# devBoard.net
KiCad netlist of a schematic drawn in EAGLE
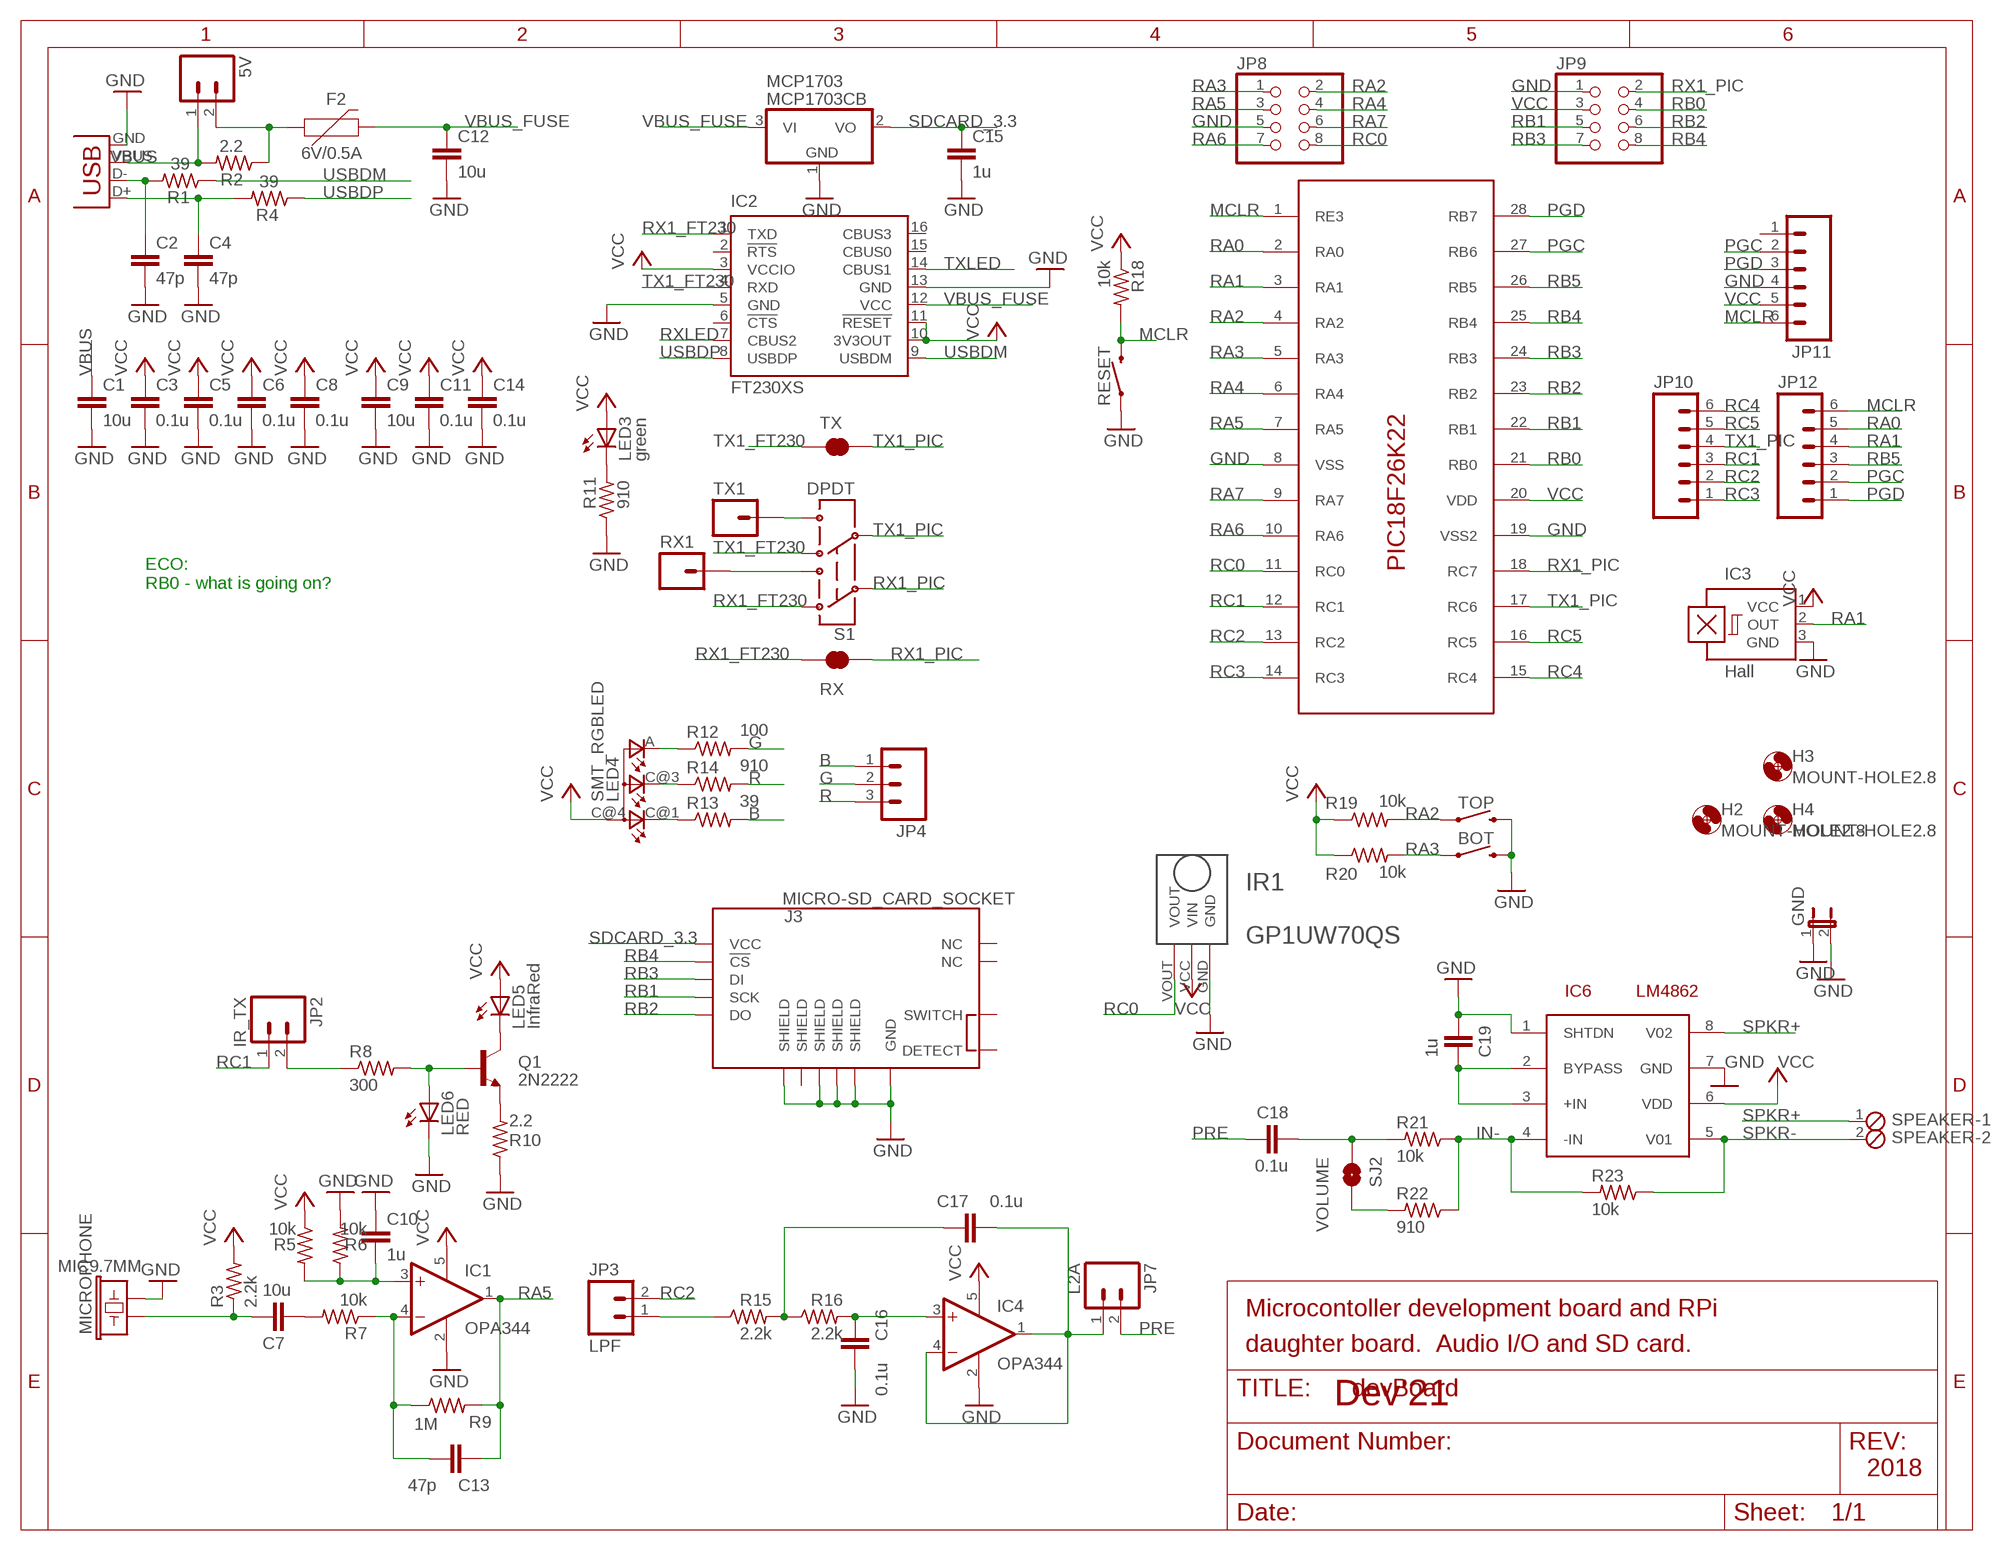
[diagram p0: schematic, sheet 1]

(export (version "E")
  (design (tool "Eeschema 10.0.6"))
  (components
    (comp (ref "5V")
      (value "M02LOCK")
      (footprint "eagle-import:1X02_LOCK")
      (libsource (lib "eagle-import") (part "M02LOCK"))
    )
    (comp (ref "BOT")
      (value "MOMENTARY-SWITCH-SPST-SMD-5.2MM")
      (footprint "eagle-import:TACTILE_SWITCH_SMD_5.2MM")
      (libsource (lib "eagle-import") (part "MOMENTARY-SWITCH-SPST-SMD-5.2MM"))
    )
    (comp (ref "C1")
      (value "10u")
      (footprint "eagle-import:C1206")
      (libsource (lib "eagle-import") (part "C-EUC1206"))
    )
    (comp (ref "C2")
      (value "47p")
      (footprint "eagle-import:C1206")
      (libsource (lib "eagle-import") (part "C-EUC1206"))
    )
    (comp (ref "C3")
      (value "0.1u")
      (footprint "eagle-import:C1206")
      (libsource (lib "eagle-import") (part "C-EUC1206"))
    )
    (comp (ref "C4")
      (value "47p")
      (footprint "eagle-import:C1206")
      (libsource (lib "eagle-import") (part "C-EUC1206"))
    )
    (comp (ref "C5")
      (value "0.1u")
      (footprint "eagle-import:C1206")
      (libsource (lib "eagle-import") (part "C-EUC1206"))
    )
    (comp (ref "C6")
      (value "0.1u")
      (footprint "eagle-import:C1206")
      (libsource (lib "eagle-import") (part "C-EUC1206"))
    )
    (comp (ref "C7")
      (value "10u")
      (footprint "eagle-import:C1206")
      (libsource (lib "eagle-import") (part "C-EUC1206"))
    )
    (comp (ref "C8")
      (value "0.1u")
      (footprint "eagle-import:C1206")
      (libsource (lib "eagle-import") (part "C-EUC1206"))
    )
    (comp (ref "C9")
      (value "10u")
      (footprint "eagle-import:C1206")
      (libsource (lib "eagle-import") (part "C-EUC1206"))
    )
    (comp (ref "C10")
      (value "1u")
      (footprint "eagle-import:C1206")
      (libsource (lib "eagle-import") (part "C-EUC1206"))
    )
    (comp (ref "C11")
      (value "0.1u")
      (footprint "eagle-import:C1206")
      (libsource (lib "eagle-import") (part "C-EUC1206"))
    )
    (comp (ref "C12")
      (value "10u")
      (footprint "eagle-import:C1206")
      (libsource (lib "eagle-import") (part "C-EUC1206"))
    )
    (comp (ref "C13")
      (value "47p")
      (footprint "eagle-import:C1206")
      (libsource (lib "eagle-import") (part "C-EUC1206"))
    )
    (comp (ref "C14")
      (value "0.1u")
      (footprint "eagle-import:C1206")
      (libsource (lib "eagle-import") (part "C-EUC1206"))
    )
    (comp (ref "C15")
      (value "1u")
      (footprint "eagle-import:C1206")
      (libsource (lib "eagle-import") (part "C-EUC1206"))
    )
    (comp (ref "C16")
      (value "0.1u")
      (footprint "eagle-import:C1206")
      (libsource (lib "eagle-import") (part "C-EUC1206"))
    )
    (comp (ref "C17")
      (value "0.1u")
      (footprint "eagle-import:C1206")
      (libsource (lib "eagle-import") (part "C-EUC1206"))
    )
    (comp (ref "C18")
      (value "0.1u")
      (footprint "eagle-import:C1206")
      (libsource (lib "eagle-import") (part "C-EUC1206"))
    )
    (comp (ref "C19")
      (value "1u")
      (footprint "eagle-import:C1206")
      (libsource (lib "eagle-import") (part "C-EUC1206"))
    )
    (comp (ref "F2")
      (value "6V/0.5A")
      (footprint "eagle-import:1206")
      (libsource (lib "eagle-import") (part "PPTC_6V500MA-2"))
    )
    (comp (ref "GND")
      (value "JP1E")
      (footprint "eagle-import:JP1")
      (libsource (lib "eagle-import") (part "JP1E"))
    )
    (comp (ref "H2")
      (value "MOUNT-HOLE2.8")
      (footprint "eagle-import:2,8")
      (libsource (lib "eagle-import") (part "MOUNT-HOLE2.8"))
    )
    (comp (ref "H3")
      (value "MOUNT-HOLE2.8")
      (footprint "eagle-import:2,8")
      (libsource (lib "eagle-import") (part "MOUNT-HOLE2.8"))
    )
    (comp (ref "H4")
      (value "MOUNT-HOLE2.8")
      (footprint "eagle-import:2,8")
      (libsource (lib "eagle-import") (part "MOUNT-HOLE2.8"))
    )
    (comp (ref "IC1")
      (value "OPA344")
      (footprint "eagle-import:SOT23-5")
      (libsource (lib "eagle-import") (part "OPA-SOT23344N"))
    )
    (comp (ref "IC2")
      (value "FT230XS")
      (footprint "eagle-import:SSOP16")
      (libsource (lib "eagle-import") (part "FT230XS"))
    )
    (comp (ref "IC3")
      (value "Hall")
      (footprint "eagle-import:SOT23-W")
      (libsource (lib "eagle-import") (part "A12?LH02"))
    )
    (comp (ref "IC4")
      (value "OPA344")
      (footprint "eagle-import:SOT23-5")
      (libsource (lib "eagle-import") (part "OPA-SOT23344N"))
    )
    (comp (ref "IC6")
      (value "LM4862")
      (footprint "eagle-import:SO08")
      (libsource (lib "eagle-import") (part "LM4862"))
    )
    (comp (ref "IR1")
      (value "GP1UW70QS")
      (footprint "eagle-import:GP1UW70QS")
      (libsource (lib "eagle-import") (part "GP1UW70QS"))
    )
    (comp (ref "J3")
      (value "MICRO-SD_CARD_SOCKET")
      (footprint "eagle-import:MICRO-SD-SOCKET")
      (libsource (lib "eagle-import") (part "MICRO-SD_CARD_SOCKET"))
    )
    (comp (ref "JP2")
      (value "IR_TX")
      (footprint "eagle-import:1X02_LOCK")
      (libsource (lib "eagle-import") (part "M02LOCK"))
    )
    (comp (ref "JP3")
      (value "LPF")
      (footprint "eagle-import:1X02_LOCK")
      (libsource (lib "eagle-import") (part "M02LOCK"))
    )
    (comp (ref "JP4")
      (value "M03LOCK")
      (footprint "eagle-import:1X03_LOCK")
      (libsource (lib "eagle-import") (part "M03LOCK"))
    )
    (comp (ref "JP7")
      (value "L2A")
      (footprint "eagle-import:1X02_LOCK")
      (libsource (lib "eagle-import") (part "M02LOCK"))
    )
    (comp (ref "JP8")
      (value "PINHD-2X4")
      (footprint "eagle-import:2X04")
      (libsource (lib "eagle-import") (part "PINHD-2X4"))
    )
    (comp (ref "JP9")
      (value "PINHD-2X4")
      (footprint "eagle-import:2X04")
      (libsource (lib "eagle-import") (part "PINHD-2X4"))
    )
    (comp (ref "JP10")
      (value "M06LOCK")
      (footprint "eagle-import:1X06_LOCK")
      (libsource (lib "eagle-import") (part "M06LOCK"))
    )
    (comp (ref "JP11")
      (value "M06LOCK")
      (footprint "eagle-import:1X06_LOCK")
      (libsource (lib "eagle-import") (part "M06LOCK"))
    )
    (comp (ref "JP12")
      (value "M06LOCK")
      (footprint "eagle-import:1X06_LOCK")
      (libsource (lib "eagle-import") (part "M06LOCK"))
    )
    (comp (ref "LED3")
      (value "green")
      (footprint "eagle-import:LED-1206")
      (libsource (lib "eagle-import") (part "LED1206"))
    )
    (comp (ref "LED4")
      (value "SMT_RGBLED")
      (footprint "eagle-import:P-LCC-4")
      (libsource (lib "eagle-import") (part "SMT_RGBLED"))
    )
    (comp (ref "LED5")
      (value "InfraRed")
      (footprint "eagle-import:LED-1206")
      (libsource (lib "eagle-import") (part "LED1206"))
    )
    (comp (ref "LED6")
      (value "RED")
      (footprint "eagle-import:LED-1206")
      (libsource (lib "eagle-import") (part "LED1206"))
    )
    (comp (ref "MCP1703")
      (value "MCP1703CB")
      (footprint "eagle-import:SOT23")
      (libsource (lib "eagle-import") (part "MCP1703CB"))
    )
    (comp (ref "MICROPHONE")
      (value "MIC9.7MM")
      (footprint "eagle-import:MIC-9.7MM")
      (libsource (lib "eagle-import") (part "MIC9.7MM"))
    )
    (comp (ref "PIC18F26K22")
      (value "PIC18F26J2228SSOP")
      (footprint "eagle-import:SSOP28DB")
      (libsource (lib "eagle-import") (part "PIC18F26J2228SSOP"))
    )
    (comp (ref "Q1")
      (value "2N2222")
      (footprint "eagle-import:SOT23-3")
      (libsource (lib "eagle-import") (part "TRANSISTOR_NPNSOT23-3"))
    )
    (comp (ref "R1")
      (value "39")
      (footprint "eagle-import:R1206")
      (libsource (lib "eagle-import") (part "R-US_R1206"))
    )
    (comp (ref "R2")
      (value "2.2")
      (footprint "eagle-import:R1206")
      (libsource (lib "eagle-import") (part "R-US_R1206"))
    )
    (comp (ref "R3")
      (value "2.2k")
      (footprint "eagle-import:R1206")
      (libsource (lib "eagle-import") (part "R-US_R1206"))
    )
    (comp (ref "R4")
      (value "39")
      (footprint "eagle-import:R1206")
      (libsource (lib "eagle-import") (part "R-US_R1206"))
    )
    (comp (ref "R5")
      (value "10k")
      (footprint "eagle-import:R1206")
      (libsource (lib "eagle-import") (part "R-US_R1206"))
    )
    (comp (ref "R6")
      (value "10k")
      (footprint "eagle-import:R1206")
      (libsource (lib "eagle-import") (part "R-US_R1206"))
    )
    (comp (ref "R7")
      (value "10k")
      (footprint "eagle-import:R1206")
      (libsource (lib "eagle-import") (part "R-US_R1206"))
    )
    (comp (ref "R8")
      (value "300")
      (footprint "eagle-import:R1206")
      (libsource (lib "eagle-import") (part "R-US_R1206"))
    )
    (comp (ref "R9")
      (value "1M")
      (footprint "eagle-import:R1206")
      (libsource (lib "eagle-import") (part "R-US_R1206"))
    )
    (comp (ref "R10")
      (value "2.2")
      (footprint "eagle-import:R1206")
      (libsource (lib "eagle-import") (part "R-US_R1206"))
    )
    (comp (ref "R11")
      (value "910")
      (footprint "eagle-import:R1206")
      (libsource (lib "eagle-import") (part "R-US_R1206"))
    )
    (comp (ref "R12")
      (value "100")
      (footprint "eagle-import:R1206")
      (libsource (lib "eagle-import") (part "R-US_R1206"))
    )
    (comp (ref "R13")
      (value "39")
      (footprint "eagle-import:R1206")
      (libsource (lib "eagle-import") (part "R-US_R1206"))
    )
    (comp (ref "R14")
      (value "910")
      (footprint "eagle-import:R1206")
      (libsource (lib "eagle-import") (part "R-US_R1206"))
    )
    (comp (ref "R15")
      (value "2.2k")
      (footprint "eagle-import:R1206")
      (libsource (lib "eagle-import") (part "R-US_R1206"))
    )
    (comp (ref "R16")
      (value "2.2k")
      (footprint "eagle-import:R1206")
      (libsource (lib "eagle-import") (part "R-US_R1206"))
    )
    (comp (ref "R18")
      (value "10k")
      (footprint "eagle-import:R1206")
      (libsource (lib "eagle-import") (part "R-US_R1206"))
    )
    (comp (ref "R19")
      (value "10k")
      (footprint "eagle-import:R1206")
      (libsource (lib "eagle-import") (part "R-US_R1206"))
    )
    (comp (ref "R20")
      (value "10k")
      (footprint "eagle-import:R1206")
      (libsource (lib "eagle-import") (part "R-US_R1206"))
    )
    (comp (ref "R21")
      (value "10k")
      (footprint "eagle-import:R1206")
      (libsource (lib "eagle-import") (part "R-US_R1206"))
    )
    (comp (ref "R22")
      (value "910")
      (footprint "eagle-import:R1206")
      (libsource (lib "eagle-import") (part "R-US_R1206"))
    )
    (comp (ref "R23")
      (value "10k")
      (footprint "eagle-import:R1206")
      (libsource (lib "eagle-import") (part "R-US_R1206"))
    )
    (comp (ref "RESET")
      (value "MOMENTARY-SWITCH-SPST-SMD-5.2MM")
      (footprint "eagle-import:TACTILE_SWITCH_SMD_5.2MM")
      (libsource (lib "eagle-import") (part "MOMENTARY-SWITCH-SPST-SMD-5.2MM"))
    )
    (comp (ref "RX")
      (value "SJ_NC")
      (footprint "eagle-import:SMT-JUMPER_2_NC_TRACE_NO-SILK")
      (libsource (lib "eagle-import") (part "JUMPER-SMT_2_NC_TRACE_NO-SILK"))
    )
    (comp (ref "RX1")
      (value "M01PTH")
      (footprint "eagle-import:1X01")
      (libsource (lib "eagle-import") (part "M01PTH"))
    )
    (comp (ref "S1")
      (value "DPDT")
      (footprint "eagle-import:AYZ0202")
      (libsource (lib "eagle-import") (part "SWITCH-DPDTAYZ0202"))
    )
    (comp (ref "SJ2")
      (value "VOLUME")
      (footprint "eagle-import:SJ_2S-NOTRACE")
      (libsource (lib "eagle-import") (part "SOLDERJUMPERNC2"))
    )
    (comp (ref "SPEAKER")
      (value "MPT2")
      (footprint "eagle-import:2POL254")
      (libsource (lib "eagle-import") (part "MPT2"))
    )
    (comp (ref "TOP")
      (value "MOMENTARY-SWITCH-SPST-SMD-5.2MM")
      (footprint "eagle-import:TACTILE_SWITCH_SMD_5.2MM")
      (libsource (lib "eagle-import") (part "MOMENTARY-SWITCH-SPST-SMD-5.2MM"))
    )
    (comp (ref "TX")
      (value "SJ_NC")
      (footprint "eagle-import:SMT-JUMPER_2_NC_TRACE_NO-SILK")
      (libsource (lib "eagle-import") (part "JUMPER-SMT_2_NC_TRACE_NO-SILK"))
    )
    (comp (ref "TX1")
      (value "M01PTH")
      (footprint "eagle-import:1X01")
      (libsource (lib "eagle-import") (part "M01PTH"))
    )
    (comp (ref "X1")
      (value "USBSMD")
      (footprint "eagle-import:USB-MINIB")
      (libsource (lib "eagle-import") (part "USBSMD"))
    )
  )
  (nets
    (net (code "1") (name "/B") (class "Default")
      (node (ref "JP4") (pin "1") (pinfunction "1_1") (pintype "passive"))
      (node (ref "R13") (pin "2") (pinfunction "2_2") (pintype "passive"))
    )
    (net (code "2") (name "/G") (class "Default")
      (node (ref "JP4") (pin "2") (pinfunction "2_2") (pintype "passive"))
      (node (ref "R12") (pin "2") (pinfunction "2_2") (pintype "passive"))
    )
    (net (code "3") (name "/IN-") (class "Default")
      (node (ref "IC6") (pin "4") (pinfunction "-IN_4") (pintype "bidirectional"))
      (node (ref "R21") (pin "1") (pinfunction "1_1") (pintype "passive"))
      (node (ref "R22") (pin "1") (pinfunction "1_1") (pintype "passive"))
      (node (ref "R23") (pin "2") (pinfunction "2_2") (pintype "passive"))
    )
    (net (code "4") (name "/MCLR") (class "Default")
      (node (ref "JP11") (pin "6") (pinfunction "6_6") (pintype "passive"))
      (node (ref "JP12") (pin "6") (pinfunction "6_6") (pintype "passive"))
      (node (ref "PIC18F26K22") (pin "1") (pinfunction "RE3_1") (pintype "bidirectional"))
      (node (ref "R18") (pin "2") (pinfunction "2_2") (pintype "passive"))
      (node (ref "RESET") (pin "3") (pinfunction "2_3") (pintype "passive"))
    )
    (net (code "5") (name "/PGC") (class "Default")
      (node (ref "JP11") (pin "2") (pinfunction "2_2") (pintype "passive"))
      (node (ref "JP12") (pin "2") (pinfunction "2_2") (pintype "passive"))
      (node (ref "PIC18F26K22") (pin "27") (pinfunction "RB6_27") (pintype "bidirectional"))
    )
    (net (code "6") (name "/PGD") (class "Default")
      (node (ref "JP11") (pin "3") (pinfunction "3_3") (pintype "passive"))
      (node (ref "JP12") (pin "1") (pinfunction "1_1") (pintype "passive"))
      (node (ref "PIC18F26K22") (pin "28") (pinfunction "RB7_28") (pintype "bidirectional"))
    )
    (net (code "7") (name "/PRE") (class "Default")
      (node (ref "C18") (pin "2") (pinfunction "2_2") (pintype "passive"))
      (node (ref "JP7") (pin "2") (pinfunction "2_2") (pintype "passive"))
    )
    (net (code "8") (name "/R") (class "Default")
      (node (ref "JP4") (pin "3") (pinfunction "3_3") (pintype "passive"))
      (node (ref "R14") (pin "2") (pinfunction "2_2") (pintype "passive"))
    )
    (net (code "9") (name "/RA0") (class "Default")
      (node (ref "JP12") (pin "5") (pinfunction "5_5") (pintype "passive"))
      (node (ref "PIC18F26K22") (pin "2") (pinfunction "RA0_2") (pintype "bidirectional"))
    )
    (net (code "10") (name "/RA1") (class "Default")
      (node (ref "IC3") (pin "2") (pinfunction "OUT_2") (pintype "output"))
      (node (ref "JP12") (pin "4") (pinfunction "4_4") (pintype "passive"))
      (node (ref "PIC18F26K22") (pin "3") (pinfunction "RA1_3") (pintype "bidirectional"))
    )
    (net (code "11") (name "/RA2") (class "Default")
      (node (ref "JP8") (pin "2") (pinfunction "2_2") (pintype "passive"))
      (node (ref "PIC18F26K22") (pin "4") (pinfunction "RA2_4") (pintype "bidirectional"))
      (node (ref "R19") (pin "2") (pinfunction "2_2") (pintype "passive"))
      (node (ref "TOP") (pin "1") (pinfunction "1_1") (pintype "passive"))
    )
    (net (code "12") (name "/RA3") (class "Default")
      (node (ref "BOT") (pin "1") (pinfunction "1_1") (pintype "passive"))
      (node (ref "JP8") (pin "1") (pinfunction "1_1") (pintype "passive"))
      (node (ref "PIC18F26K22") (pin "5") (pinfunction "RA3_5") (pintype "bidirectional"))
      (node (ref "R20") (pin "2") (pinfunction "2_2") (pintype "passive"))
    )
    (net (code "13") (name "/RA4") (class "Default")
      (node (ref "JP8") (pin "4") (pinfunction "4_4") (pintype "passive"))
      (node (ref "PIC18F26K22") (pin "6") (pinfunction "RA4_6") (pintype "bidirectional"))
    )
    (net (code "14") (name "/RA5") (class "Default")
      (node (ref "C13") (pin "2") (pinfunction "2_2") (pintype "passive"))
      (node (ref "IC1") (pin "1") (pinfunction "OUT_1") (pintype "output"))
      (node (ref "JP8") (pin "3") (pinfunction "3_3") (pintype "passive"))
      (node (ref "PIC18F26K22") (pin "7") (pinfunction "RA5_7") (pintype "bidirectional"))
      (node (ref "R9") (pin "2") (pinfunction "2_2") (pintype "passive"))
    )
    (net (code "15") (name "/RA6") (class "Default")
      (node (ref "JP8") (pin "7") (pinfunction "7_7") (pintype "passive"))
      (node (ref "PIC18F26K22") (pin "10") (pinfunction "RA6_10") (pintype "bidirectional"))
    )
    (net (code "16") (name "/RA7") (class "Default")
      (node (ref "JP8") (pin "6") (pinfunction "6_6") (pintype "passive"))
      (node (ref "PIC18F26K22") (pin "9") (pinfunction "RA7_9") (pintype "bidirectional"))
    )
    (net (code "17") (name "/RB0") (class "Default")
      (node (ref "JP9") (pin "4") (pinfunction "4_4") (pintype "passive"))
      (node (ref "PIC18F26K22") (pin "21") (pinfunction "RB0_21") (pintype "bidirectional"))
    )
    (net (code "18") (name "/RB1") (class "Default")
      (node (ref "J3") (pin "SCLK") (pinfunction "SCK_SCLK") (pintype "bidirectional"))
      (node (ref "JP9") (pin "5") (pinfunction "5_5") (pintype "passive"))
      (node (ref "PIC18F26K22") (pin "22") (pinfunction "RB1_22") (pintype "bidirectional"))
    )
    (net (code "19") (name "/RB2") (class "Default")
      (node (ref "J3") (pin "DO") (pinfunction "DO_DO") (pintype "bidirectional"))
      (node (ref "JP9") (pin "6") (pinfunction "6_6") (pintype "passive"))
      (node (ref "PIC18F26K22") (pin "23") (pinfunction "RB2_23") (pintype "bidirectional"))
    )
    (net (code "20") (name "/RB3") (class "Default")
      (node (ref "J3") (pin "DI") (pinfunction "DI_DI") (pintype "bidirectional"))
      (node (ref "JP9") (pin "7") (pinfunction "7_7") (pintype "passive"))
      (node (ref "PIC18F26K22") (pin "24") (pinfunction "RB3_24") (pintype "bidirectional"))
    )
    (net (code "21") (name "/RB4") (class "Default")
      (node (ref "J3") (pin "CS") (pinfunction "~{CS}_CS") (pintype "bidirectional"))
      (node (ref "JP9") (pin "8") (pinfunction "8_8") (pintype "passive"))
      (node (ref "PIC18F26K22") (pin "25") (pinfunction "RB4_25") (pintype "bidirectional"))
    )
    (net (code "22") (name "/RB5") (class "Default")
      (node (ref "JP12") (pin "3") (pinfunction "3_3") (pintype "passive"))
      (node (ref "PIC18F26K22") (pin "26") (pinfunction "RB5_26") (pintype "bidirectional"))
    )
    (net (code "23") (name "/RC0") (class "Default")
      (node (ref "IR1") (pin "VOUT") (pinfunction "VOUT_VOUT") (pintype "bidirectional"))
      (node (ref "JP8") (pin "8") (pinfunction "8_8") (pintype "passive"))
      (node (ref "PIC18F26K22") (pin "11") (pinfunction "RC0_11") (pintype "bidirectional"))
    )
    (net (code "24") (name "/RC1") (class "Default")
      (node (ref "JP10") (pin "3") (pinfunction "3_3") (pintype "passive"))
      (node (ref "JP2") (pin "1") (pinfunction "1_1") (pintype "passive"))
      (node (ref "PIC18F26K22") (pin "12") (pinfunction "RC1_12") (pintype "bidirectional"))
    )
    (net (code "25") (name "/RC2") (class "Default")
      (node (ref "JP10") (pin "2") (pinfunction "2_2") (pintype "passive"))
      (node (ref "JP3") (pin "2") (pinfunction "2_2") (pintype "passive"))
      (node (ref "PIC18F26K22") (pin "13") (pinfunction "RC2_13") (pintype "bidirectional"))
    )
    (net (code "26") (name "/RC3") (class "Default")
      (node (ref "JP10") (pin "1") (pinfunction "1_1") (pintype "passive"))
      (node (ref "PIC18F26K22") (pin "14") (pinfunction "RC3_14") (pintype "bidirectional"))
    )
    (net (code "27") (name "/RC4") (class "Default")
      (node (ref "JP10") (pin "6") (pinfunction "6_6") (pintype "passive"))
      (node (ref "PIC18F26K22") (pin "15") (pinfunction "RC4_15") (pintype "bidirectional"))
    )
    (net (code "28") (name "/RC5") (class "Default")
      (node (ref "JP10") (pin "5") (pinfunction "5_5") (pintype "passive"))
      (node (ref "PIC18F26K22") (pin "16") (pinfunction "RC5_16") (pintype "bidirectional"))
    )
    (net (code "29") (name "/RX1_FT230") (class "Default")
      (node (ref "IC2") (pin "1") (pinfunction "TXD_1") (pintype "output"))
      (node (ref "RX") (pin "1") (pinfunction "1_1") (pintype "passive"))
      (node (ref "S1") (pin "1") (pinfunction "1_1") (pintype "bidirectional"))
    )
    (net (code "30") (name "/RX1_PIC") (class "Default")
      (node (ref "JP9") (pin "2") (pinfunction "2_2") (pintype "passive"))
      (node (ref "PIC18F26K22") (pin "18") (pinfunction "RC7_18") (pintype "bidirectional"))
      (node (ref "RX") (pin "2") (pinfunction "2_2") (pintype "passive"))
      (node (ref "S1") (pin "2") (pinfunction "2_2") (pintype "bidirectional"))
    )
    (net (code "31") (name "/RXLED") (class "Default")
      (node (ref "IC2") (pin "7") (pinfunction "CBUS2_7") (pintype "bidirectional"))
    )
    (net (code "32") (name "/SDCARD_3.3") (class "Default")
      (node (ref "C15") (pin "1") (pinfunction "1_1") (pintype "passive"))
      (node (ref "J3") (pin "VCC") (pinfunction "VCC_VCC") (pintype "bidirectional"))
      (node (ref "MCP1703") (pin "2") (pinfunction "VO_2") (pintype "passive"))
    )
    (net (code "33") (name "/SPKR+") (class "Default")
      (node (ref "IC6") (pin "8") (pinfunction "V02_8") (pintype "bidirectional"))
      (node (ref "SPEAKER") (pin "1") (pinfunction "1_1") (pintype "passive"))
    )
    (net (code "34") (name "/SPKR-") (class "Default")
      (node (ref "IC6") (pin "5") (pinfunction "V01_5") (pintype "bidirectional"))
      (node (ref "R23") (pin "1") (pinfunction "1_1") (pintype "passive"))
      (node (ref "SPEAKER") (pin "2") (pinfunction "1_2") (pintype "passive"))
    )
    (net (code "35") (name "/TX1_FT230") (class "Default")
      (node (ref "IC2") (pin "4") (pinfunction "RXD_4") (pintype "input"))
      (node (ref "S1") (pin "4") (pinfunction "4_4") (pintype "bidirectional"))
      (node (ref "TX") (pin "1") (pinfunction "1_1") (pintype "passive"))
    )
    (net (code "36") (name "/TX1_PIC") (class "Default")
      (node (ref "JP10") (pin "4") (pinfunction "4_4") (pintype "passive"))
      (node (ref "PIC18F26K22") (pin "17") (pinfunction "RC6_17") (pintype "bidirectional"))
      (node (ref "S1") (pin "5") (pinfunction "5_5") (pintype "bidirectional"))
      (node (ref "TX") (pin "2") (pinfunction "2_2") (pintype "passive"))
    )
    (net (code "37") (name "/TXLED") (class "Default")
      (node (ref "IC2") (pin "14") (pinfunction "CBUS1_14") (pintype "bidirectional"))
    )
    (net (code "38") (name "/USBDM") (class "Default")
      (node (ref "IC2") (pin "9") (pinfunction "USBDM_9") (pintype "input"))
      (node (ref "R1") (pin "1") (pinfunction "1_1") (pintype "passive"))
    )
    (net (code "39") (name "/USBDP") (class "Default")
      (node (ref "IC2") (pin "8") (pinfunction "USBDP_8") (pintype "input"))
      (node (ref "R4") (pin "1") (pinfunction "1_1") (pintype "passive"))
    )
    (net (code "40") (name "/VBUS") (class "Default")
      (node (ref "5V") (pin "1") (pinfunction "1_1") (pintype "passive"))
      (node (ref "C1") (pin "1") (pinfunction "1_1") (pintype "passive"))
      (node (ref "R2") (pin "2") (pinfunction "2_2") (pintype "passive"))
      (node (ref "X1") (pin "VBUS") (pinfunction "VBUS_VBUS") (pintype "bidirectional"))
    )
    (net (code "41") (name "/VBUS_FUSE") (class "Default")
      (node (ref "C12") (pin "1") (pinfunction "1_1") (pintype "passive"))
      (node (ref "F2") (pin "2") (pinfunction "2_2") (pintype "bidirectional"))
      (node (ref "IC2") (pin "12") (pinfunction "VCC_12") (pintype "power_in"))
      (node (ref "MCP1703") (pin "3") (pinfunction "VI_3") (pintype "input"))
    )
    (net (code "42") (name "GND") (class "Default")
      (node (ref "BOT") (pin "3") (pinfunction "2_3") (pintype "passive"))
      (node (ref "C1") (pin "2") (pinfunction "2_2") (pintype "passive"))
      (node (ref "C10") (pin "1") (pinfunction "1_1") (pintype "passive"))
      (node (ref "C11") (pin "2") (pinfunction "2_2") (pintype "passive"))
      (node (ref "C12") (pin "2") (pinfunction "2_2") (pintype "passive"))
      (node (ref "C14") (pin "2") (pinfunction "2_2") (pintype "passive"))
      (node (ref "C15") (pin "2") (pinfunction "2_2") (pintype "passive"))
      (node (ref "C16") (pin "1") (pinfunction "1_1") (pintype "passive"))
      (node (ref "C19") (pin "2") (pinfunction "2_2") (pintype "passive"))
      (node (ref "C2") (pin "2") (pinfunction "2_2") (pintype "passive"))
      (node (ref "C3") (pin "2") (pinfunction "2_2") (pintype "passive"))
      (node (ref "C4") (pin "2") (pinfunction "2_2") (pintype "passive"))
      (node (ref "C5") (pin "2") (pinfunction "2_2") (pintype "passive"))
      (node (ref "C6") (pin "2") (pinfunction "2_2") (pintype "passive"))
      (node (ref "C8") (pin "2") (pinfunction "2_2") (pintype "passive"))
      (node (ref "C9") (pin "2") (pinfunction "2_2") (pintype "passive"))
      (node (ref "GND") (pin "1") (pinfunction "1_1") (pintype "passive"))
      (node (ref "GND") (pin "2") (pinfunction "2_2") (pintype "passive"))
      (node (ref "IC1") (pin "2") (pinfunction "V-_2") (pintype "power_in"))
      (node (ref "IC2") (pin "13") (pinfunction "GND_13") (pintype "power_in"))
      (node (ref "IC2") (pin "5") (pinfunction "GND_5") (pintype "power_in"))
      (node (ref "IC3") (pin "3") (pinfunction "GND_3") (pintype "power_in"))
      (node (ref "IC4") (pin "2") (pinfunction "V-_2") (pintype "power_in"))
      (node (ref "IC6") (pin "1") (pinfunction "SHTDN_1") (pintype "bidirectional"))
      (node (ref "IC6") (pin "7") (pinfunction "GND_7") (pintype "power_in"))
      (node (ref "IR1") (pin "GND") (pinfunction "GND_GND") (pintype "bidirectional"))
      (node (ref "J3") (pin "GND") (pinfunction "GND_GND") (pintype "bidirectional"))
      (node (ref "J3") (pin "SHIELD1") (pinfunction "SHIELD_SHIELD1") (pintype "bidirectional"))
      (node (ref "J3") (pin "SHIELD3") (pinfunction "SHIELD_SHIELD3") (pintype "bidirectional"))
      (node (ref "J3") (pin "SHIELD4") (pinfunction "SHIELD_SHIELD4") (pintype "bidirectional"))
      (node (ref "J3") (pin "SHIELD5") (pinfunction "SHIELD_SHIELD5") (pintype "bidirectional"))
      (node (ref "JP11") (pin "4") (pinfunction "4_4") (pintype "passive"))
      (node (ref "JP8") (pin "5") (pinfunction "5_5") (pintype "passive"))
      (node (ref "JP9") (pin "1") (pinfunction "1_1") (pintype "passive"))
      (node (ref "LED6") (pin "C") (pinfunction "C_C") (pintype "passive"))
      (node (ref "MCP1703") (pin "1") (pinfunction "GND_1") (pintype "passive"))
      (node (ref "MICROPHONE") (pin "2") (pinfunction "2_2") (pintype "passive"))
      (node (ref "PIC18F26K22") (pin "19") (pinfunction "VSS2_19") (pintype "bidirectional"))
      (node (ref "PIC18F26K22") (pin "8") (pinfunction "VSS_8") (pintype "bidirectional"))
      (node (ref "R10") (pin "1") (pinfunction "1_1") (pintype "passive"))
      (node (ref "R11") (pin "1") (pinfunction "1_1") (pintype "passive"))
      (node (ref "R6") (pin "2") (pinfunction "2_2") (pintype "passive"))
      (node (ref "RESET") (pin "1") (pinfunction "1_1") (pintype "passive"))
      (node (ref "TOP") (pin "3") (pinfunction "2_3") (pintype "passive"))
      (node (ref "X1") (pin "GND") (pinfunction "GND_GND") (pintype "bidirectional"))
    )
    (net (code "43") (name "Net-(5V-Pad2)") (class "Default")
      (node (ref "5V") (pin "2") (pinfunction "2_2") (pintype "passive"))
      (node (ref "F2") (pin "1") (pinfunction "1_1") (pintype "bidirectional"))
      (node (ref "R2") (pin "1") (pinfunction "1_1") (pintype "passive"))
    )
    (net (code "44") (name "Net-(C2-Pad1)") (class "Default")
      (node (ref "C2") (pin "1") (pinfunction "1_1") (pintype "passive"))
      (node (ref "R1") (pin "2") (pinfunction "2_2") (pintype "passive"))
      (node (ref "X1") (pin "D-") (pinfunction "D-_D-") (pintype "bidirectional"))
    )
    (net (code "45") (name "Net-(C4-Pad1)") (class "Default")
      (node (ref "C4") (pin "1") (pinfunction "1_1") (pintype "passive"))
      (node (ref "R4") (pin "2") (pinfunction "2_2") (pintype "passive"))
      (node (ref "X1") (pin "D+") (pinfunction "D+_D+") (pintype "bidirectional"))
    )
    (net (code "46") (name "Net-(C7-Pad1)") (class "Default")
      (node (ref "C7") (pin "1") (pinfunction "1_1") (pintype "passive"))
      (node (ref "MICROPHONE") (pin "1") (pinfunction "1_1") (pintype "passive"))
      (node (ref "R3") (pin "1") (pinfunction "1_1") (pintype "passive"))
    )
    (net (code "47") (name "Net-(C7-Pad2)") (class "Default")
      (node (ref "C7") (pin "2") (pinfunction "2_2") (pintype "passive"))
      (node (ref "R7") (pin "2") (pinfunction "2_2") (pintype "passive"))
    )
    (net (code "48") (name "Net-(C17-Pad2)") (class "Default")
      (node (ref "C17") (pin "2") (pinfunction "2_2") (pintype "passive"))
      (node (ref "R15") (pin "2") (pinfunction "2_2") (pintype "passive"))
      (node (ref "R16") (pin "1") (pinfunction "1_1") (pintype "passive"))
    )
    (net (code "49") (name "Net-(C18-Pad1)") (class "Default")
      (node (ref "C18") (pin "1") (pinfunction "1_1") (pintype "passive"))
      (node (ref "R21") (pin "2") (pinfunction "2_2") (pintype "passive"))
      (node (ref "SJ2") (pin "1") (pinfunction "1_1") (pintype "passive"))
    )
    (net (code "50") (name "Net-(IC1-+IN)") (class "Default")
      (node (ref "C10") (pin "2") (pinfunction "2_2") (pintype "passive"))
      (node (ref "IC1") (pin "3") (pinfunction "+IN_3") (pintype "input"))
      (node (ref "R5") (pin "2") (pinfunction "2_2") (pintype "passive"))
      (node (ref "R6") (pin "1") (pinfunction "1_1") (pintype "passive"))
    )
    (net (code "51") (name "Net-(IC1--IN)") (class "Default")
      (node (ref "C13") (pin "1") (pinfunction "1_1") (pintype "passive"))
      (node (ref "IC1") (pin "4") (pinfunction "-IN_4") (pintype "input"))
      (node (ref "R7") (pin "1") (pinfunction "1_1") (pintype "passive"))
      (node (ref "R9") (pin "1") (pinfunction "1_1") (pintype "passive"))
    )
    (net (code "52") (name "Net-(IC4-+IN)") (class "Default")
      (node (ref "C16") (pin "2") (pinfunction "2_2") (pintype "passive"))
      (node (ref "IC4") (pin "3") (pinfunction "+IN_3") (pintype "input"))
      (node (ref "R16") (pin "2") (pinfunction "2_2") (pintype "passive"))
    )
    (net (code "53") (name "Net-(IC4--IN)") (class "Default")
      (node (ref "C17") (pin "1") (pinfunction "1_1") (pintype "passive"))
      (node (ref "IC4") (pin "1") (pinfunction "OUT_1") (pintype "output"))
      (node (ref "IC4") (pin "4") (pinfunction "-IN_4") (pintype "input"))
      (node (ref "JP7") (pin "1") (pinfunction "1_1") (pintype "passive"))
    )
    (net (code "54") (name "Net-(IC6-+IN)") (class "Default")
      (node (ref "C19") (pin "1") (pinfunction "1_1") (pintype "passive"))
      (node (ref "IC6") (pin "2") (pinfunction "BYPASS_2") (pintype "bidirectional"))
      (node (ref "IC6") (pin "3") (pinfunction "+IN_3") (pintype "bidirectional"))
    )
    (net (code "55") (name "Net-(JP2-Pad2)") (class "Default")
      (node (ref "JP2") (pin "2") (pinfunction "2_2") (pintype "passive"))
      (node (ref "R8") (pin "1") (pinfunction "1_1") (pintype "passive"))
    )
    (net (code "56") (name "Net-(JP3-Pad1)") (class "Default")
      (node (ref "JP3") (pin "1") (pinfunction "1_1") (pintype "passive"))
      (node (ref "R15") (pin "1") (pinfunction "1_1") (pintype "passive"))
    )
    (net (code "57") (name "Net-(LED3-PadC)") (class "Default")
      (node (ref "LED3") (pin "C") (pinfunction "C_C") (pintype "passive"))
      (node (ref "R11") (pin "2") (pinfunction "2_2") (pintype "passive"))
    )
    (net (code "58") (name "Net-(LED4-CBLUE)") (class "Default")
      (node (ref "LED4") (pin "C@3") (pinfunction "CBLUE_C@3") (pintype "passive"))
      (node (ref "R14") (pin "1") (pinfunction "1_1") (pintype "passive"))
    )
    (net (code "59") (name "Net-(LED4-CGREEN)") (class "Default")
      (node (ref "LED4") (pin "A") (pinfunction "CGREEN_A") (pintype "passive"))
      (node (ref "R12") (pin "1") (pinfunction "1_1") (pintype "passive"))
    )
    (net (code "60") (name "Net-(LED4-CRED)") (class "Default")
      (node (ref "LED4") (pin "C@1") (pinfunction "CRED_C@1") (pintype "passive"))
      (node (ref "R13") (pin "1") (pinfunction "1_1") (pintype "passive"))
    )
    (net (code "61") (name "Net-(Q1-B)") (class "Default")
      (node (ref "LED6") (pin "A") (pinfunction "A_A") (pintype "passive"))
      (node (ref "Q1") (pin "1") (pinfunction "B_1") (pintype "passive"))
      (node (ref "R8") (pin "2") (pinfunction "2_2") (pintype "passive"))
    )
    (net (code "62") (name "Net-(Q1-C)") (class "Default")
      (node (ref "LED5") (pin "C") (pinfunction "C_C") (pintype "passive"))
      (node (ref "Q1") (pin "3") (pinfunction "C_3") (pintype "passive"))
    )
    (net (code "63") (name "Net-(Q1-E)") (class "Default")
      (node (ref "Q1") (pin "2") (pinfunction "E_2") (pintype "passive"))
      (node (ref "R10") (pin "2") (pinfunction "2_2") (pintype "passive"))
    )
    (net (code "64") (name "Net-(R22-Pad2)") (class "Default")
      (node (ref "R22") (pin "2") (pinfunction "2_2") (pintype "passive"))
      (node (ref "SJ2") (pin "2") (pinfunction "2_2") (pintype "passive"))
    )
    (net (code "65") (name "Net-(RX1-Pad1)") (class "Default")
      (node (ref "RX1") (pin "1") (pinfunction "1_1") (pintype "passive"))
      (node (ref "S1") (pin "3") (pinfunction "3_3") (pintype "bidirectional"))
    )
    (net (code "66") (name "Net-(S1-Pad6)") (class "Default")
      (node (ref "S1") (pin "6") (pinfunction "6_6") (pintype "bidirectional"))
      (node (ref "TX1") (pin "1") (pinfunction "1_1") (pintype "passive"))
    )
    (net (code "67") (name "VCC") (class "Default")
      (node (ref "C11") (pin "1") (pinfunction "1_1") (pintype "passive"))
      (node (ref "C14") (pin "1") (pinfunction "1_1") (pintype "passive"))
      (node (ref "C3") (pin "1") (pinfunction "1_1") (pintype "passive"))
      (node (ref "C5") (pin "1") (pinfunction "1_1") (pintype "passive"))
      (node (ref "C6") (pin "1") (pinfunction "1_1") (pintype "passive"))
      (node (ref "C8") (pin "1") (pinfunction "1_1") (pintype "passive"))
      (node (ref "C9") (pin "1") (pinfunction "1_1") (pintype "passive"))
      (node (ref "IC1") (pin "5") (pinfunction "V+_5") (pintype "power_in"))
      (node (ref "IC2") (pin "10") (pinfunction "3V3OUT_10") (pintype "output"))
      (node (ref "IC2") (pin "11") (pinfunction "~{RESET}_11") (pintype "input"))
      (node (ref "IC2") (pin "3") (pinfunction "VCCIO_3") (pintype "power_in"))
      (node (ref "IC3") (pin "1") (pinfunction "VCC_1") (pintype "power_in"))
      (node (ref "IC4") (pin "5") (pinfunction "V+_5") (pintype "power_in"))
      (node (ref "IC6") (pin "6") (pinfunction "VDD_6") (pintype "power_in"))
      (node (ref "IR1") (pin "VCC") (pinfunction "VIN_VCC") (pintype "bidirectional"))
      (node (ref "JP11") (pin "5") (pinfunction "5_5") (pintype "passive"))
      (node (ref "JP9") (pin "3") (pinfunction "3_3") (pintype "passive"))
      (node (ref "LED3") (pin "A") (pinfunction "A_A") (pintype "passive"))
      (node (ref "LED4") (pin "C@4") (pinfunction "A_C@4") (pintype "passive"))
      (node (ref "LED5") (pin "A") (pinfunction "A_A") (pintype "passive"))
      (node (ref "PIC18F26K22") (pin "20") (pinfunction "VDD_20") (pintype "bidirectional"))
      (node (ref "R18") (pin "1") (pinfunction "1_1") (pintype "passive"))
      (node (ref "R19") (pin "1") (pinfunction "1_1") (pintype "passive"))
      (node (ref "R20") (pin "1") (pinfunction "1_1") (pintype "passive"))
      (node (ref "R3") (pin "2") (pinfunction "2_2") (pintype "passive"))
      (node (ref "R5") (pin "1") (pinfunction "1_1") (pintype "passive"))
    )
    (net (code "68") (name "unconnected-(IC2-CBUS0-Pad15)") (class "Default")
      (node (ref "IC2") (pin "15") (pinfunction "CBUS0_15") (pintype "bidirectional"))
    )
    (net (code "69") (name "unconnected-(IC2-CBUS3-Pad16)") (class "Default")
      (node (ref "IC2") (pin "16") (pinfunction "CBUS3_16") (pintype "bidirectional"))
    )
    (net (code "70") (name "unconnected-(IC2-~{CTS}-Pad6)") (class "Default")
      (node (ref "IC2") (pin "6") (pinfunction "~{CTS}_6") (pintype "input"))
    )
    (net (code "71") (name "unconnected-(IC2-~{RTS}-Pad2)") (class "Default")
      (node (ref "IC2") (pin "2") (pinfunction "~{RTS}_2") (pintype "output"))
    )
    (net (code "72") (name "unconnected-(J3-NC-PadNC1)") (class "Default")
      (node (ref "J3") (pin "NC1") (pinfunction "NC_NC1") (pintype "bidirectional"))
    )
    (net (code "73") (name "unconnected-(J3-NC-PadNC2)") (class "Default")
      (node (ref "J3") (pin "NC2") (pinfunction "NC_NC2") (pintype "bidirectional"))
    )
    (net (code "74") (name "unconnected-(J3-PadDETECT)") (class "Default")
      (node (ref "J3") (pin "DETECT") (pinfunction "DETECT_DETECT") (pintype "bidirectional"))
    )
    (net (code "75") (name "unconnected-(J3-PadSWITCH)") (class "Default")
      (node (ref "J3") (pin "SWITCH") (pinfunction "SWITCH_SWITCH") (pintype "bidirectional"))
    )
    (net (code "76") (name "unconnected-(J3-SHIELD-PadSHIELD2)") (class "Default")
      (node (ref "J3") (pin "SHIELD2") (pinfunction "SHIELD_SHIELD2") (pintype "bidirectional"))
    )
    (net (code "77") (name "unconnected-(JP11-Pad1)") (class "Default")
      (node (ref "JP11") (pin "1") (pinfunction "1_1") (pintype "passive"))
    )
  )
)
